# Radio.net
KiCad netlist of a schematic drawn in Altium Designer
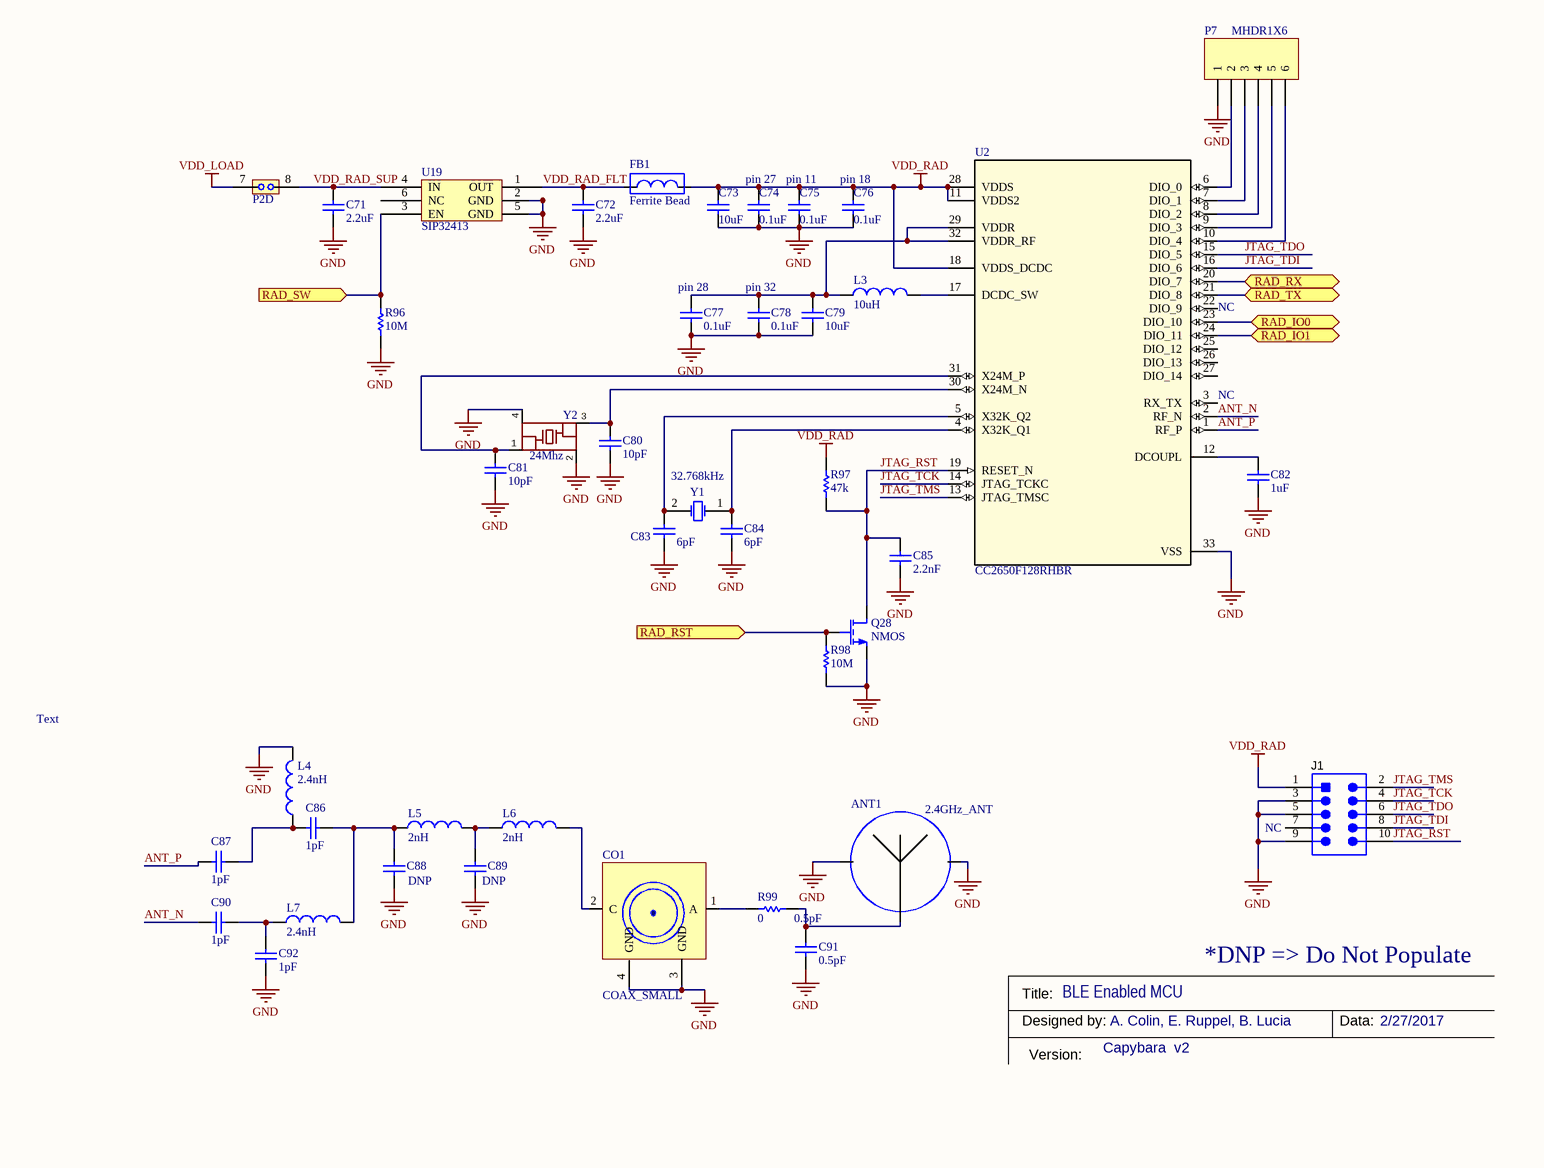
[diagram p0: Radio.SchDoc, bottom left]

(export (version "E")
  (design (tool "Eeschema 10.0.6"))
  (components
    (comp (ref "ANT1")
      (value "2.4GHz_ANT")
      (footprint "IIF_INV")
      (libsource (lib "Sprite") (part "2.4GHz_ANT"))
    )
    (comp (ref "C71")
      (value "2.2uF")
      (footprint "0603")
      (description "Ceramic Capacitor (Surface Mount)")
      (fields
        (field (name "MANUFACTURER") "Murata Electronics North America")
        (field (name "MANUFACTURER PART NUMBER") "GRM188R61C225KE15D")
      )
      (libsource (lib "DRP_Basic_2014") (part "Cap"))
    )
    (comp (ref "C72")
      (value "2.2uF")
      (footprint "0603")
      (description "Ceramic Capacitor (Surface Mount)")
      (fields
        (field (name "MANUFACTURER") "Murata Electronics North America")
        (field (name "MANUFACTURER PART NUMBER") "GRM188R61C225KE15D")
      )
      (libsource (lib "DRP_Basic_2014") (part "Cap"))
    )
    (comp (ref "C73")
      (value "10uF")
      (footprint "0603")
      (description "Ceramic Capacitor (Surface Mount)")
      (fields
        (field (name "MANUFACTURER") "Murata Electronics North America")
        (field (name "MANUFACTURER PART NUMBER") "GRM188R60J106ME47D")
      )
      (libsource (lib "DRP_Basic_2014") (part "Cap"))
    )
    (comp (ref "C74")
      (value "0.1uF")
      (footprint "0603")
      (description "Ceramic Capacitor (Surface Mount)")
      (fields
        (field (name "MANUFACTURER") "Murata Electronics North America")
        (field (name "MANUFACTURER PART NUMBER") "GRM188R71C104KA01D")
      )
      (libsource (lib "DRP_Basic_2014") (part "Cap"))
    )
    (comp (ref "C75")
      (value "0.1uF")
      (footprint "0603")
      (description "Ceramic Capacitor (Surface Mount)")
      (fields
        (field (name "MANUFACTURER") "Murata Electronics North America")
        (field (name "MANUFACTURER PART NUMBER") "GRM188R71C104KA01D")
      )
      (libsource (lib "DRP_Basic_2014") (part "Cap"))
    )
    (comp (ref "C76")
      (value "0.1uF")
      (footprint "0603")
      (description "Ceramic Capacitor (Surface Mount)")
      (fields
        (field (name "MANUFACTURER") "Murata Electronics North America")
        (field (name "MANUFACTURER PART NUMBER") "GRM188R71C104KA01D")
      )
      (libsource (lib "DRP_Basic_2014") (part "Cap"))
    )
    (comp (ref "C77")
      (value "0.1uF")
      (footprint "0603")
      (description "Ceramic Capacitor (Surface Mount)")
      (fields
        (field (name "MANUFACTURER") "Murata Electronics North America")
        (field (name "MANUFACTURER PART NUMBER") "GRM188R71C104KA01D")
      )
      (libsource (lib "DRP_Basic_2014") (part "Cap"))
    )
    (comp (ref "C78")
      (value "0.1uF")
      (footprint "0603")
      (description "Ceramic Capacitor (Surface Mount)")
      (fields
        (field (name "MANUFACTURER") "Murata Electronics North America")
        (field (name "MANUFACTURER PART NUMBER") "GRM188R71C104KA01D")
      )
      (libsource (lib "DRP_Basic_2014") (part "Cap"))
    )
    (comp (ref "C79")
      (value "10uF")
      (footprint "0603")
      (description "Ceramic Capacitor (Surface Mount)")
      (fields
        (field (name "MANUFACTURER") "Murata Electronics North America")
        (field (name "MANUFACTURER PART NUMBER") "GRM188R60J106ME47D")
      )
      (libsource (lib "DRP_Basic_2014") (part "Cap"))
    )
    (comp (ref "C80")
      (value "10pF")
      (footprint "0402")
      (description "Ceramic Capacitor (Surface Mount)")
      (fields (field (name "MANUFACTURER") "AvX") (field (name "MANUFACTURER PART NUMBER") "04025A100MAT2A"))
      (libsource (lib "DRP_Basic_2014") (part "Cap"))
    )
    (comp (ref "C81")
      (value "10pF")
      (footprint "0402")
      (description "Ceramic Capacitor (Surface Mount)")
      (fields (field (name "MANUFACTURER") "AvX") (field (name "MANUFACTURER PART NUMBER") "04025A100MAT2A"))
      (libsource (lib "DRP_Basic_2014") (part "Cap"))
    )
    (comp (ref "C82")
      (value "1uF")
      (footprint "0603")
      (description "Ceramic Capacitor (Surface Mount)")
      (fields
        (field (name "MANUFACTURER") "Murata Electronics North America")
        (field (name "MANUFACTURER PART NUMBER") "GRM188R61A105KA61D")
      )
      (libsource (lib "DRP_Basic_2014") (part "Cap"))
    )
    (comp (ref "C83")
      (value "6pF")
      (footprint "0402")
      (description "Ceramic Capacitor (Surface Mount)")
      (fields
        (field (name "MANUFACTURER") "Murata Electronics North America")
        (field (name "MANUFACTURER PART NUMBER") "GRM1555C1H6R0CA01D")
      )
      (libsource (lib "DRP_Basic_2014") (part "Cap"))
    )
    (comp (ref "C84")
      (value "6pF")
      (footprint "0402")
      (description "Ceramic Capacitor (Surface Mount)")
      (fields
        (field (name "MANUFACTURER") "Murata Electronics North America")
        (field (name "MANUFACTURER PART NUMBER") "GRM1555C1H6R0CA01D")
      )
      (libsource (lib "DRP_Basic_2014") (part "Cap"))
    )
    (comp (ref "C85")
      (value "2.2nF")
      (footprint "0603")
      (description "Ceramic Capacitor (Surface Mount)")
      (fields
        (field (name "MANUFACTURER") "Murata Electronics North America")
        (field (name "MANUFACTURER PART NUMBER") "GRM1885C1H222JA01D")
      )
      (libsource (lib "DRP_Basic_2014") (part "Cap"))
    )
    (comp (ref "C86")
      (value "1pF")
      (footprint "0402")
      (description "Ceramic Capacitor (Surface Mount)")
      (fields
        (field (name "DIGI-KEY PART NUMBER") "712-1266-1-ND")
        (field (name "MANUFACTURER") "Murata Electronics")
      )
      (libsource (lib "DRP_Basic_2014") (part "Cap"))
    )
    (comp (ref "C87")
      (value "1pF")
      (footprint "0402")
      (description "Ceramic Capacitor (Surface Mount)")
      (fields
        (field (name "DIGI-KEY PART NUMBER") "712-1266-1-ND")
        (field (name "MANUFACTURER") "Murata Electronics")
      )
      (libsource (lib "DRP_Basic_2014") (part "Cap"))
    )
    (comp (ref "C88")
      (value "Cap")
      (footprint "0402")
      (description "Ceramic Capacitor (Surface Mount)")
      (fields (field (name "MANUFACTURER") "Generic Ceramic Chip Cap (TBD)") (field (name "NOTE") "DNP"))
      (libsource (lib "DRP_Basic_2014") (part "Cap"))
    )
    (comp (ref "C89")
      (value "Cap")
      (footprint "0402")
      (description "Ceramic Capacitor (Surface Mount)")
      (fields (field (name "MANUFACTURER") "Generic Ceramic Chip Cap (TBD)") (field (name "NOTE") "DNP"))
      (libsource (lib "DRP_Basic_2014") (part "Cap"))
    )
    (comp (ref "C90")
      (value "1pF")
      (footprint "0402")
      (description "Ceramic Capacitor (Surface Mount)")
      (fields
        (field (name "DIGI-KEY PART NUMBER") "712-1266-1-ND")
        (field (name "MANUFACTURER") "Murata Electronics")
      )
      (libsource (lib "DRP_Basic_2014") (part "Cap"))
    )
    (comp (ref "C91")
      (value "0.5pF")
      (footprint "0402")
      (description "Ceramic Capacitor (Surface Mount)")
      (fields
        (field (name "MANUFACTURER") "Murata Electronics")
        (field (name "NOTE") "0.5pF")
        (field (name "DISTRIBUTOR PART NUMBER") "490-6263-1-nd")
      )
      (libsource (lib "DRP_Basic_2014") (part "Cap"))
    )
    (comp (ref "C92")
      (value "1pF")
      (footprint "0402")
      (description "Ceramic Capacitor (Surface Mount)")
      (fields
        (field (name "DIGI-KEY PART NUMBER") "712-1266-1-ND")
        (field (name "MANUFACTURER") "Murata Electronics")
      )
      (libsource (lib "DRP_Basic_2014") (part "Cap"))
    )
    (comp (ref "CO1")
      (value "COAX_SMALL")
      (footprint "COAX SMALL_v2")
      (description "ms-156hf")
      (fields
        (field (name "DISTRIBUTOR PART NUMBER") "798-MS156HF20")
        (field (name "MANUFACTURER") "Hirose Connector")
      )
      (libsource (lib "Sprite") (part "COAX_SMALL"))
    )
    (comp (ref "FB1")
      (value "Ferrite Bead")
      (footprint "0603")
      (description "Ferrite bead, RF choke")
      (fields
        (field (name "DIGI-KEY PART NUMBER") "490-5216-1-ND")
        (field (name "MANUFACTURER") "Murata Electronics North America")
      )
      (libsource (lib "DRP_Basic_2014") (part "Ferrite Bead"))
    )
    (comp (ref "J1")
      (value "~")
      (footprint "JTAG_V3")
      (description "Header, 50mil, 5x2, Gold, TH")
      (fields
        (field (name "MANUFACTURER") "Samtec Inc.")
        (field (name "DISTRIBUTOR PART NUMBER") "SAM8798-ND")
        (field (name "PUBLISHER") "Texas Instruments")
      )
      (libsource (lib "Connectors_Sullins") (part "GRPB052VWVN-RC"))
    )
    (comp (ref "L3")
      (value "10uH")
      (footprint "0603")
      (description "Inductor (Surface Mount)")
      (fields
        (field (name "DIGI-KEY PART NUMBER") "587-2243-1-nd")
        (field (name "MANUFACTURER") "Taiyo Yuden")
      )
      (libsource (lib "DRP_Basic_2014") (part "Ind"))
    )
    (comp (ref "L4")
      (value "2.4nH")
      (footprint "0402")
      (description "Inductor (Surface Mount)")
      (fields
        (field (name "DIGI-KEY PART NUMBER") "490-8389-1-ND")
        (field (name "MANUFACTURER") "Murata Electronics North America")
      )
      (libsource (lib "DRP_Basic_2014") (part "Ind"))
    )
    (comp (ref "L5")
      (value "2nH")
      (footprint "0402")
      (description "Inductor (Surface Mount)")
      (fields
        (field (name "MANUFACTURER") "Murata Electronics North America")
        (field (name "MANUFACTURER PART NUMBER") "LQG15HS2N0S02D")
      )
      (libsource (lib "DRP_Basic_2014") (part "Ind"))
    )
    (comp (ref "L6")
      (value "2nH")
      (footprint "0402")
      (description "Inductor (Surface Mount)")
      (fields
        (field (name "MANUFACTURER") "Murata Electronics North America")
        (field (name "MANUFACTURER PART NUMBER") "LQG15HS2N0S02D")
      )
      (libsource (lib "DRP_Basic_2014") (part "Ind"))
    )
    (comp (ref "L7")
      (value "2.4nH")
      (footprint "0402")
      (description "Inductor (Surface Mount)")
      (fields
        (field (name "DIGI-KEY PART NUMBER") "490-8389-1-ND")
        (field (name "MANUFACTURER") "Murata Electronics North America")
      )
      (libsource (lib "DRP_Basic_2014") (part "Ind"))
    )
    (comp (ref "P2") (value "JMPHDR_8") (footprint "MHDR2X8") (libsource (lib "Sprite") (part "JMPHDR_8")))
    (comp (ref "P7")
      (value "MHDR1X6")
      (footprint "MHDR1X6")
      (description "Header, 6-Pin")
      (fields
        (field (name "DIGI-KEY PART NUMBER") "952-3359-ND")
        (field (name "DISTRIBUTOR PART NUMBER") "855-M52-5000645")
        (field (name "PUBLISHER") "Altium Limited")
      )
      (libsource (lib "Miscellaneous Connectors") (part "MHDR1X6"))
    )
    (comp (ref "Q28")
      (value "NMOS")
      (footprint "SOT-523-3")
      (description "N-Channel MOSFET")
      (fields (field (name "MANUFACTURER PART NUMBER") "FDY302NZ") (field (name "MANUFACTURER") "Fairchild"))
      (libsource (lib "DRP_Basic_2014") (part "MOSFET-N"))
    )
    (comp (ref "R96")
      (value "10M")
      (footprint "0603")
      (description "Chip Resistor (Surface Mount)")
      (fields
        (field (name "MANUFACTURER") "Yageo")
        (field (name "MANUFACTURER PART NUMBER") "RC0603JR-0710ML")
      )
      (libsource (lib "DRP_Basic_2014") (part "Res"))
    )
    (comp (ref "R97")
      (value "47k")
      (footprint "0603")
      (description "Chip Resistor (Surface Mount)")
      (fields
        (field (name "MANUFACTURER") "Yageo")
        (field (name "MANUFACTURER PART NUMBER") "RT0603DRD0747KL")
      )
      (libsource (lib "WISP_AD10") (part "Res"))
    )
    (comp (ref "R98")
      (value "10M")
      (footprint "0603")
      (description "Chip Resistor (Surface Mount)")
      (fields
        (field (name "MANUFACTURER") "Yageo")
        (field (name "MANUFACTURER PART NUMBER") "RC0603JR-0710ML")
      )
      (libsource (lib "DRP_Basic_2014") (part "Res"))
    )
    (comp (ref "R99")
      (value "0")
      (footprint "0402")
      (description "Chip Resistor (Surface Mount)")
      (fields
        (field (name "MANUFACTURER") "Panasonic Electronic Components")
        (field (name "MANUFACTURER PART NUMBER") "ERJ-2GE0R00X")
      )
      (libsource (lib "DRP_Basic_2014") (part "Res"))
    )
    (comp (ref "U2")
      (value "CC2650F128RHBR")
      (footprint "RHB0032E_NV")
      (description "Imported")
      (fields
        (field (name "ALTERNATE_PARTNUMBER") "CC2650F128RHBT")
        (field (name "MANUFACTURER") "Texas Instruments")
      )
      (libsource (lib "cc2650_rhb") (part "CC2650F128RHBR"))
    )
    (comp (ref "U19")
      (value "SIP32413")
      (footprint "SC70-6")
      (fields
        (field (name "DIGI-KEY PART NUMBER") "SIP32431DR3-T1GE3CT-ND")
        (field (name "DISTRIBUTOR PART NUMBER") "781-SIP32431DR3-GE3")
        (field (name "MANUFACTURER") "Vishay Semiconductors")
      )
      (libsource (lib "Sprite") (part "SIP32431"))
    )
    (comp (ref "Y1")
      (value "32.768kHz")
      (footprint "XTAL - 2Pin [3.2mm x 1.5mm]")
      (description "Crystal Oscillator")
      (fields
        (field (name "DISTRIBUTOR PART NUMBER") "520-.327-6-34QCST")
        (field (name "MANUFACTURER") "ECS Inc.")
      )
      (libsource (lib "Miscellaneous Devices") (part "XTAL"))
    )
    (comp (ref "Y2")
      (value "24Mhz")
      (footprint "XTAL - 4Pin [2.5mm x 2.0mm]")
      (fields
        (field (name "DISTRIBUTOR PART NUMBER") "520-ECS-240-8-36CKM")
        (field (name "MANUFACTURER") "ECS Inc.")
        (field (name "MANUFACTURER PART NUMBER") "ECS-240-8-36CKM-TR")
      )
      (libsource (lib "ABM11") (part "ABM11_CERAMIC_SMD_CRYSTALABM11"))
    )
  )
  (nets
    (net (code "1") (name "/ANT_N") (class "Default")
      (node (ref "C90") (pin "2") (pinfunction "2_2") (pintype "passive"))
      (node (ref "U2") (pin "2") (pinfunction "RF_N_2") (pintype "bidirectional"))
    )
    (net (code "2") (name "/ANT_P") (class "Default")
      (node (ref "C87") (pin "2") (pinfunction "2_2") (pintype "passive"))
      (node (ref "U2") (pin "1") (pinfunction "RF_P_1") (pintype "bidirectional"))
    )
    (net (code "3") (name "/JTAG_RST") (class "Default")
      (node (ref "C85") (pin "1") (pinfunction "1_1") (pintype "passive"))
      (node (ref "J1") (pin "10") (pinfunction "10_10") (pintype "passive"))
      (node (ref "Q28") (pin "3") (pinfunction "D_3") (pintype "passive"))
      (node (ref "R97") (pin "1") (pinfunction "1_1") (pintype "passive"))
      (node (ref "U2") (pin "19") (pinfunction "RESET_N_19") (pintype "input"))
    )
    (net (code "4") (name "/JTAG_TCK") (class "Default")
      (node (ref "J1") (pin "4") (pinfunction "4_4") (pintype "passive"))
      (node (ref "U2") (pin "14") (pinfunction "JTAG_TCKC_14") (pintype "bidirectional"))
    )
    (net (code "5") (name "/JTAG_TDI") (class "Default")
      (node (ref "J1") (pin "8") (pinfunction "8_8") (pintype "passive"))
      (node (ref "U2") (pin "16") (pinfunction "DIO_6_16") (pintype "bidirectional"))
    )
    (net (code "6") (name "/JTAG_TDO") (class "Default")
      (node (ref "J1") (pin "6") (pinfunction "6_6") (pintype "passive"))
      (node (ref "U2") (pin "15") (pinfunction "DIO_5_15") (pintype "bidirectional"))
    )
    (net (code "7") (name "/JTAG_TMS") (class "Default")
      (node (ref "J1") (pin "2") (pinfunction "2_2") (pintype "passive"))
      (node (ref "U2") (pin "13") (pinfunction "JTAG_TMSC_13") (pintype "bidirectional"))
    )
    (net (code "8") (name "/RAD_IO0") (class "Default")
      (node (ref "U2") (pin "23") (pinfunction "DIO_10_23") (pintype "bidirectional"))
    )
    (net (code "9") (name "/RAD_IO1") (class "Default")
      (node (ref "U2") (pin "24") (pinfunction "DIO_11_24") (pintype "bidirectional"))
    )
    (net (code "10") (name "/RAD_RST") (class "Default")
      (node (ref "Q28") (pin "1") (pinfunction "G_1") (pintype "passive"))
      (node (ref "R98") (pin "2") (pinfunction "2_2") (pintype "passive"))
    )
    (net (code "11") (name "/RAD_RX") (class "Default")
      (node (ref "U2") (pin "20") (pinfunction "DIO_7_20") (pintype "bidirectional"))
    )
    (net (code "12") (name "/RAD_SW") (class "Default")
      (node (ref "R96") (pin "2") (pinfunction "2_2") (pintype "passive"))
      (node (ref "U19") (pin "3") (pinfunction "EN_3") (pintype "passive"))
    )
    (net (code "13") (name "/RAD_TX") (class "Default")
      (node (ref "U2") (pin "21") (pinfunction "DIO_8_21") (pintype "bidirectional"))
    )
    (net (code "14") (name "/VDD_RAD_FLT") (class "Default")
      (node (ref "C72") (pin "2") (pinfunction "2_2") (pintype "passive"))
      (node (ref "FB1") (pin "1") (pinfunction "1_1") (pintype "passive"))
      (node (ref "U19") (pin "1") (pinfunction "OUT_1") (pintype "passive"))
    )
    (net (code "15") (name "/VDD_RAD_SUP") (class "Default")
      (node (ref "C71") (pin "2") (pinfunction "2_2") (pintype "passive"))
      (node (ref "P2") (pin "8") (pinfunction "8_8") (pintype "passive"))
      (node (ref "U19") (pin "4") (pinfunction "IN_4") (pintype "passive"))
    )
    (net (code "16") (name "GND") (class "Default")
      (node (ref "ANT1") (pin "2") (pinfunction "GND_2") (pintype "passive"))
      (node (ref "ANT1") (pin "3") (pinfunction "GND_3") (pintype "passive"))
      (node (ref "C71") (pin "1") (pinfunction "1_1") (pintype "passive"))
      (node (ref "C72") (pin "1") (pinfunction "1_1") (pintype "passive"))
      (node (ref "C73") (pin "1") (pinfunction "1_1") (pintype "passive"))
      (node (ref "C74") (pin "1") (pinfunction "1_1") (pintype "passive"))
      (node (ref "C75") (pin "1") (pinfunction "1_1") (pintype "passive"))
      (node (ref "C76") (pin "1") (pinfunction "1_1") (pintype "passive"))
      (node (ref "C77") (pin "1") (pinfunction "1_1") (pintype "passive"))
      (node (ref "C78") (pin "1") (pinfunction "1_1") (pintype "passive"))
      (node (ref "C79") (pin "1") (pinfunction "1_1") (pintype "passive"))
      (node (ref "C80") (pin "1") (pinfunction "1_1") (pintype "passive"))
      (node (ref "C81") (pin "2") (pinfunction "2_2") (pintype "passive"))
      (node (ref "C82") (pin "1") (pinfunction "1_1") (pintype "passive"))
      (node (ref "C83") (pin "1") (pinfunction "1_1") (pintype "passive"))
      (node (ref "C84") (pin "1") (pinfunction "1_1") (pintype "passive"))
      (node (ref "C85") (pin "2") (pinfunction "2_2") (pintype "passive"))
      (node (ref "C88") (pin "1") (pinfunction "1_1") (pintype "passive"))
      (node (ref "C89") (pin "1") (pinfunction "1_1") (pintype "passive"))
      (node (ref "C91") (pin "1") (pinfunction "1_1") (pintype "passive"))
      (node (ref "C92") (pin "1") (pinfunction "1_1") (pintype "passive"))
      (node (ref "CO1") (pin "3") (pinfunction "GND_3") (pintype "passive"))
      (node (ref "CO1") (pin "4") (pinfunction "GND_4") (pintype "passive"))
      (node (ref "J1") (pin "3") (pinfunction "3_3") (pintype "passive"))
      (node (ref "J1") (pin "5") (pinfunction "5_5") (pintype "passive"))
      (node (ref "J1") (pin "9") (pinfunction "9_9") (pintype "passive"))
      (node (ref "L4") (pin "2") (pinfunction "2_2") (pintype "passive"))
      (node (ref "P7") (pin "1") (pinfunction "1_1") (pintype "passive"))
      (node (ref "Q28") (pin "2") (pinfunction "S_2") (pintype "passive"))
      (node (ref "R96") (pin "1") (pinfunction "1_1") (pintype "passive"))
      (node (ref "R98") (pin "1") (pinfunction "1_1") (pintype "passive"))
      (node (ref "U19") (pin "2") (pinfunction "GND_2") (pintype "passive"))
      (node (ref "U19") (pin "5") (pinfunction "GND_5") (pintype "passive"))
      (node (ref "U2") (pin "33") (pinfunction "VSS_33") (pintype "power_in"))
      (node (ref "Y2") (pin "2") (pinfunction "GROUND2_2") (pintype "passive"))
      (node (ref "Y2") (pin "4") (pinfunction "GROUND4_4") (pintype "passive"))
    )
    (net (code "17") (name "Net-(ANT1-ANT)") (class "Default")
      (node (ref "ANT1") (pin "1") (pinfunction "ANT_1") (pintype "passive"))
      (node (ref "C91") (pin "2") (pinfunction "2_2") (pintype "passive"))
      (node (ref "R99") (pin "2") (pinfunction "2_2") (pintype "passive"))
    )
    (net (code "18") (name "Net-(C86-Pad1)") (class "Default")
      (node (ref "C86") (pin "1") (pinfunction "1_1") (pintype "passive"))
      (node (ref "C88") (pin "2") (pinfunction "2_2") (pintype "passive"))
      (node (ref "L5") (pin "1") (pinfunction "1_1") (pintype "passive"))
      (node (ref "L7") (pin "2") (pinfunction "2_2") (pintype "passive"))
    )
    (net (code "19") (name "Net-(C86-Pad2)") (class "Default")
      (node (ref "C86") (pin "2") (pinfunction "2_2") (pintype "passive"))
      (node (ref "C87") (pin "1") (pinfunction "1_1") (pintype "passive"))
      (node (ref "L4") (pin "1") (pinfunction "1_1") (pintype "passive"))
    )
    (net (code "20") (name "Net-(C89-Pad2)") (class "Default")
      (node (ref "C89") (pin "2") (pinfunction "2_2") (pintype "passive"))
      (node (ref "L5") (pin "2") (pinfunction "2_2") (pintype "passive"))
      (node (ref "L6") (pin "1") (pinfunction "1_1") (pintype "passive"))
    )
    (net (code "21") (name "Net-(C90-Pad1)") (class "Default")
      (node (ref "C90") (pin "1") (pinfunction "1_1") (pintype "passive"))
      (node (ref "C92") (pin "2") (pinfunction "2_2") (pintype "passive"))
      (node (ref "L7") (pin "1") (pinfunction "1_1") (pintype "passive"))
    )
    (net (code "22") (name "Net-(CO1-A)") (class "Default")
      (node (ref "CO1") (pin "1") (pinfunction "A_1") (pintype "passive"))
      (node (ref "R99") (pin "1") (pinfunction "1_1") (pintype "passive"))
    )
    (net (code "23") (name "Net-(CO1-C)") (class "Default")
      (node (ref "CO1") (pin "2") (pinfunction "C_2") (pintype "passive"))
      (node (ref "L6") (pin "2") (pinfunction "2_2") (pintype "passive"))
    )
    (net (code "24") (name "Net-(U2-DCDC_SW)") (class "Default")
      (node (ref "L3") (pin "2") (pinfunction "2_2") (pintype "passive"))
      (node (ref "U2") (pin "17") (pinfunction "DCDC_SW_17") (pintype "power_in"))
    )
    (net (code "25") (name "Net-(U2-DCOUPL)") (class "Default")
      (node (ref "C82") (pin "2") (pinfunction "2_2") (pintype "passive"))
      (node (ref "U2") (pin "12") (pinfunction "DCOUPL_12") (pintype "power_in"))
    )
    (net (code "26") (name "Net-(U2-DIO_0)") (class "Default")
      (node (ref "P7") (pin "2") (pinfunction "2_2") (pintype "passive"))
      (node (ref "U2") (pin "6") (pinfunction "DIO_0_6") (pintype "bidirectional"))
    )
    (net (code "27") (name "Net-(U2-DIO_1)") (class "Default")
      (node (ref "P7") (pin "3") (pinfunction "3_3") (pintype "passive"))
      (node (ref "U2") (pin "7") (pinfunction "DIO_1_7") (pintype "bidirectional"))
    )
    (net (code "28") (name "Net-(U2-DIO_2)") (class "Default")
      (node (ref "P7") (pin "4") (pinfunction "4_4") (pintype "passive"))
      (node (ref "U2") (pin "8") (pinfunction "DIO_2_8") (pintype "bidirectional"))
    )
    (net (code "29") (name "Net-(U2-DIO_3)") (class "Default")
      (node (ref "P7") (pin "5") (pinfunction "5_5") (pintype "passive"))
      (node (ref "U2") (pin "9") (pinfunction "DIO_3_9") (pintype "bidirectional"))
    )
    (net (code "30") (name "Net-(U2-DIO_4)") (class "Default")
      (node (ref "P7") (pin "6") (pinfunction "6_6") (pintype "passive"))
      (node (ref "U2") (pin "10") (pinfunction "DIO_4_10") (pintype "bidirectional"))
    )
    (net (code "31") (name "Net-(U2-VDDR)") (class "Default")
      (node (ref "C77") (pin "2") (pinfunction "2_2") (pintype "passive"))
      (node (ref "C78") (pin "2") (pinfunction "2_2") (pintype "passive"))
      (node (ref "C79") (pin "2") (pinfunction "2_2") (pintype "passive"))
      (node (ref "L3") (pin "1") (pinfunction "1_1") (pintype "passive"))
      (node (ref "U2") (pin "29") (pinfunction "VDDR_29") (pintype "power_in"))
      (node (ref "U2") (pin "32") (pinfunction "VDDR_RF_32") (pintype "power_in"))
    )
    (net (code "32") (name "Net-(U2-X24M_N)") (class "Default")
      (node (ref "C80") (pin "2") (pinfunction "2_2") (pintype "passive"))
      (node (ref "U2") (pin "30") (pinfunction "X24M_N_30") (pintype "bidirectional"))
      (node (ref "Y2") (pin "3") (pinfunction "P3_3") (pintype "passive"))
    )
    (net (code "33") (name "Net-(U2-X24M_P)") (class "Default")
      (node (ref "C81") (pin "1") (pinfunction "1_1") (pintype "passive"))
      (node (ref "U2") (pin "31") (pinfunction "X24M_P_31") (pintype "bidirectional"))
      (node (ref "Y2") (pin "1") (pinfunction "P$1_1") (pintype "passive"))
    )
    (net (code "34") (name "Net-(U2-X32K_Q1)") (class "Default")
      (node (ref "C84") (pin "2") (pinfunction "2_2") (pintype "passive"))
      (node (ref "U2") (pin "4") (pinfunction "X32K_Q1_4") (pintype "bidirectional"))
      (node (ref "Y1") (pin "1") (pinfunction "OSC1_1") (pintype "passive"))
    )
    (net (code "35") (name "Net-(U2-X32K_Q2)") (class "Default")
      (node (ref "C83") (pin "2") (pinfunction "2_2") (pintype "passive"))
      (node (ref "U2") (pin "5") (pinfunction "X32K_Q2_5") (pintype "bidirectional"))
      (node (ref "Y1") (pin "2") (pinfunction "OSC2_2") (pintype "passive"))
    )
    (net (code "36") (name "VDD_LOAD") (class "Default")
      (node (ref "P2") (pin "7") (pinfunction "7_7") (pintype "passive"))
    )
    (net (code "37") (name "VDD_RAD") (class "Default")
      (node (ref "C73") (pin "2") (pinfunction "2_2") (pintype "passive"))
      (node (ref "C74") (pin "2") (pinfunction "2_2") (pintype "passive"))
      (node (ref "C75") (pin "2") (pinfunction "2_2") (pintype "passive"))
      (node (ref "C76") (pin "2") (pinfunction "2_2") (pintype "passive"))
      (node (ref "FB1") (pin "2") (pinfunction "2_2") (pintype "passive"))
      (node (ref "J1") (pin "1") (pinfunction "1_1") (pintype "passive"))
      (node (ref "R97") (pin "2") (pinfunction "2_2") (pintype "passive"))
      (node (ref "U2") (pin "11") (pinfunction "VDDS2_11") (pintype "power_in"))
      (node (ref "U2") (pin "18") (pinfunction "VDDS_DCDC_18") (pintype "power_in"))
      (node (ref "U2") (pin "28") (pinfunction "VDDS_28") (pintype "power_in"))
    )
    (net (code "38") (name "unconnected-(J1-Pad7)") (class "Default")
      (node (ref "J1") (pin "7") (pinfunction "7_7") (pintype "passive"))
    )
    (net (code "39") (name "unconnected-(U2-DIO_9-Pad22)") (class "Default")
      (node (ref "U2") (pin "22") (pinfunction "DIO_9_22") (pintype "bidirectional"))
    )
    (net (code "40") (name "unconnected-(U2-DIO_12-Pad25)") (class "Default")
      (node (ref "U2") (pin "25") (pinfunction "DIO_12_25") (pintype "bidirectional"))
    )
    (net (code "41") (name "unconnected-(U2-DIO_13-Pad26)") (class "Default")
      (node (ref "U2") (pin "26") (pinfunction "DIO_13_26") (pintype "bidirectional"))
    )
    (net (code "42") (name "unconnected-(U2-DIO_14-Pad27)") (class "Default")
      (node (ref "U2") (pin "27") (pinfunction "DIO_14_27") (pintype "bidirectional"))
    )
    (net (code "43") (name "unconnected-(U2-RX_TX-Pad3)") (class "Default")
      (node (ref "U2") (pin "3") (pinfunction "RX_TX_3") (pintype "bidirectional"))
    )
    (net (code "44") (name "unconnected-(U19-NC-Pad6)") (class "Default")
      (node (ref "U19") (pin "6") (pinfunction "NC_6") (pintype "passive"))
    )
  )
)
